# BSPD.net
KiCad netlist of a schematic drawn in EAGLE
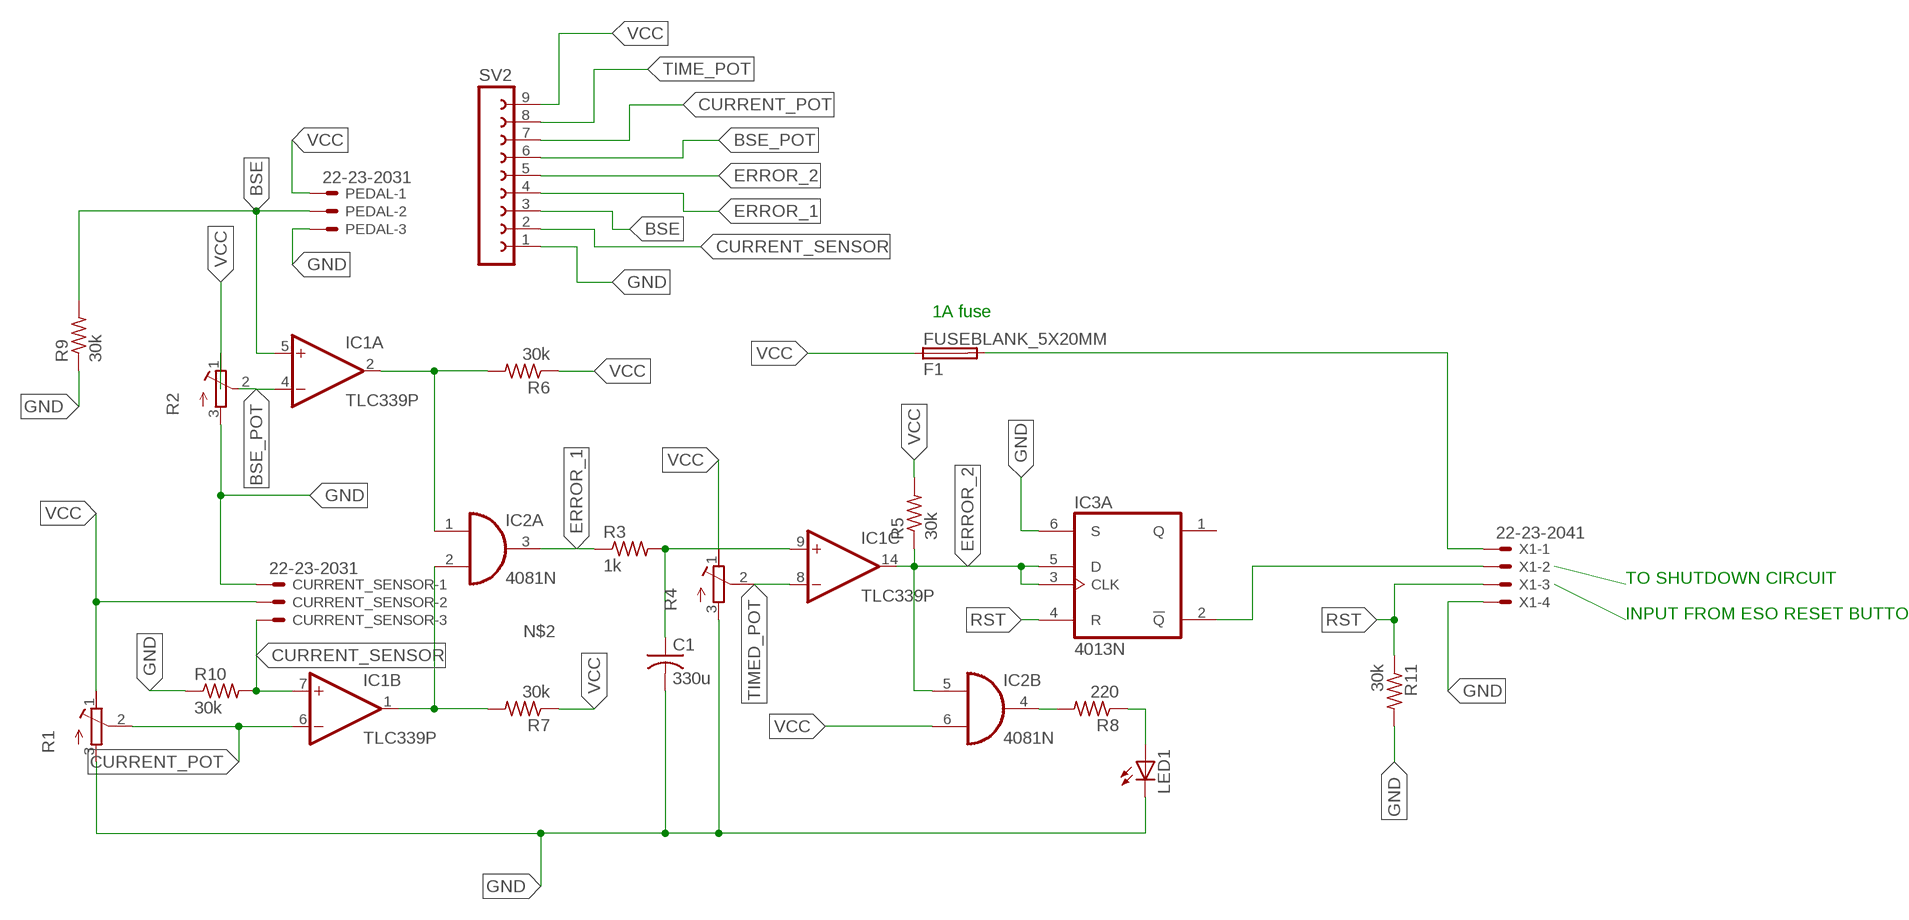
[diagram p0: schematic, sheet 1]

(export (version "E")
  (design (tool "Eeschema 10.0.6"))
  (components
    (comp (ref "C1")
      (value "330u")
      (footprint "eagle-import:C225-108X268")
      (libsource (lib "eagle-import") (part "C-US225-108X268"))
    )
    (comp (ref "CURRENT_SENSOR")
      (value "22-23-2031")
      (footprint "eagle-import:22-23-2031")
      (fields (field (name "MF") "MOLEX"))
      (libsource (lib "eagle-import") (part "22-23-2031"))
    )
    (comp (ref "F1")
      (value "FUSEBLANK_5X20MM")
      (footprint "eagle-import:FUSE_HOLDER_5X20MM")
      (libsource (lib "eagle-import") (part "FUSEBLANK_5X20MM"))
    )
    (comp (ref "IC1")
      (value "TLC339P")
      (footprint "eagle-import:DIL14")
      (libsource (lib "eagle-import") (part "TLC339P"))
    )
    (comp (ref "IC2")
      (value "4081N")
      (footprint "eagle-import:DIL14")
      (libsource (lib "eagle-import") (part "4081N"))
    )
    (comp (ref "IC3")
      (value "4013N")
      (footprint "eagle-import:DIL14")
      (libsource (lib "eagle-import") (part "4013N"))
    )
    (comp (ref "LED1")
      (value "LED5MM")
      (footprint "eagle-import:LED5MM")
      (libsource (lib "eagle-import") (part "LED5MM"))
    )
    (comp (ref "PEDAL")
      (value "22-23-2031")
      (footprint "eagle-import:22-23-2031")
      (fields (field (name "MF") "MOLEX"))
      (libsource (lib "eagle-import") (part "22-23-2031"))
    )
    (comp (ref "R1")
      (value "R-TRIMM3006P")
      (footprint "eagle-import:RTRIM3006P")
      (libsource (lib "eagle-import") (part "R-TRIMM3006P"))
    )
    (comp (ref "R2")
      (value "R-TRIMM43P")
      (footprint "eagle-import:RTRIM43P")
      (libsource (lib "eagle-import") (part "R-TRIMM43P"))
    )
    (comp (ref "R3")
      (value "1k")
      (footprint "eagle-import:0207_12")
      (libsource (lib "eagle-import") (part "R-US_0207/12"))
    )
    (comp (ref "R4")
      (value "R-TRIMM3006P")
      (footprint "eagle-import:RTRIM3006P")
      (libsource (lib "eagle-import") (part "R-TRIMM3006P"))
    )
    (comp (ref "R5")
      (value "30k")
      (footprint "eagle-import:0207_12")
      (libsource (lib "eagle-import") (part "R-US_0207/12"))
    )
    (comp (ref "R6")
      (value "30k")
      (footprint "eagle-import:0207_12")
      (libsource (lib "eagle-import") (part "R-US_0207/12"))
    )
    (comp (ref "R7")
      (value "30k")
      (footprint "eagle-import:0207_12")
      (libsource (lib "eagle-import") (part "R-US_0207/12"))
    )
    (comp (ref "R8")
      (value "220")
      (footprint "eagle-import:0207_12")
      (libsource (lib "eagle-import") (part "R-US_0207/12"))
    )
    (comp (ref "R9")
      (value "30k")
      (footprint "eagle-import:0207_12")
      (libsource (lib "eagle-import") (part "R-US_0207/12"))
    )
    (comp (ref "R10")
      (value "30k")
      (footprint "eagle-import:0207_12")
      (libsource (lib "eagle-import") (part "R-US_0207/12"))
    )
    (comp (ref "R11")
      (value "30k")
      (footprint "eagle-import:0207_12")
      (libsource (lib "eagle-import") (part "R-US_0207/12"))
    )
    (comp (ref "SV2")
      (value "FE09W")
      (footprint "eagle-import:FE09W")
      (libsource (lib "eagle-import") (part "FE09W"))
    )
    (comp (ref "X1")
      (value "22-23-2041")
      (footprint "eagle-import:22-23-2041")
      (fields (field (name "MF") "MOLEX"))
      (libsource (lib "eagle-import") (part "22-23-2041"))
    )
  )
  (nets
    (net (code "1") (name "/N$2") (class "Default")
      (node (ref "IC1") (pin "1") (pinfunction "OUT_1") (pintype "output"))
      (node (ref "IC2") (pin "2") (pinfunction "I1_2") (pintype "input"))
      (node (ref "R7") (pin "2") (pinfunction "2_2") (pintype "passive"))
    )
    (net (code "2") (name "BSE") (class "Default")
      (node (ref "IC1") (pin "5") (pinfunction "+IN_5") (pintype "input"))
      (node (ref "PEDAL") (pin "2") (pinfunction "S_2") (pintype "passive"))
      (node (ref "R9") (pin "2") (pinfunction "2_2") (pintype "passive"))
      (node (ref "SV2") (pin "3") (pinfunction "3_3") (pintype "passive"))
    )
    (net (code "3") (name "BSE_POT") (class "Default")
      (node (ref "IC1") (pin "4") (pinfunction "-IN_4") (pintype "input"))
      (node (ref "R2") (pin "2") (pinfunction "S_2") (pintype "passive"))
      (node (ref "SV2") (pin "6") (pinfunction "6_6") (pintype "passive"))
    )
    (net (code "4") (name "CURRENT_POT") (class "Default")
      (node (ref "IC1") (pin "6") (pinfunction "-IN_6") (pintype "input"))
      (node (ref "R1") (pin "2") (pinfunction "S_2") (pintype "passive"))
      (node (ref "SV2") (pin "7") (pinfunction "7_7") (pintype "passive"))
    )
    (net (code "5") (name "CURRENT_SENSOR") (class "Default")
      (node (ref "CURRENT_SENSOR") (pin "3") (pinfunction "S_3") (pintype "passive"))
      (node (ref "IC1") (pin "7") (pinfunction "+IN_7") (pintype "input"))
      (node (ref "R10") (pin "2") (pinfunction "2_2") (pintype "passive"))
      (node (ref "SV2") (pin "2") (pinfunction "2_2") (pintype "passive"))
    )
    (net (code "6") (name "ERROR_1") (class "Default")
      (node (ref "IC2") (pin "3") (pinfunction "O_3") (pintype "output"))
      (node (ref "R3") (pin "1") (pinfunction "1_1") (pintype "passive"))
      (node (ref "SV2") (pin "4") (pinfunction "4_4") (pintype "passive"))
    )
    (net (code "7") (name "ERROR_2") (class "Default")
      (node (ref "IC1") (pin "14") (pinfunction "OUT_14") (pintype "output"))
      (node (ref "IC2") (pin "5") (pinfunction "I0_5") (pintype "input"))
      (node (ref "IC3") (pin "3") (pinfunction "CLK_3") (pintype "input"))
      (node (ref "IC3") (pin "5") (pinfunction "D_5") (pintype "input"))
      (node (ref "R5") (pin "1") (pinfunction "1_1") (pintype "passive"))
      (node (ref "SV2") (pin "5") (pinfunction "5_5") (pintype "passive"))
    )
    (net (code "8") (name "GND") (class "Default")
      (node (ref "C1") (pin "2") (pinfunction "2_2") (pintype "passive"))
      (node (ref "CURRENT_SENSOR") (pin "1") (pinfunction "S_1") (pintype "passive"))
      (node (ref "IC3") (pin "6") (pinfunction "S_6") (pintype "input"))
      (node (ref "LED1") (pin "K") (pinfunction "C_K") (pintype "passive"))
      (node (ref "PEDAL") (pin "3") (pinfunction "S_3") (pintype "passive"))
      (node (ref "R1") (pin "3") (pinfunction "A_3") (pintype "passive"))
      (node (ref "R10") (pin "1") (pinfunction "1_1") (pintype "passive"))
      (node (ref "R11") (pin "2") (pinfunction "2_2") (pintype "passive"))
      (node (ref "R2") (pin "3") (pinfunction "A_3") (pintype "passive"))
      (node (ref "R4") (pin "3") (pinfunction "A_3") (pintype "passive"))
      (node (ref "R9") (pin "1") (pinfunction "1_1") (pintype "passive"))
      (node (ref "SV2") (pin "1") (pinfunction "1_1") (pintype "passive"))
      (node (ref "X1") (pin "4") (pinfunction "S_4") (pintype "passive"))
    )
    (net (code "9") (name "Net-(IC1A-OUT)") (class "Default")
      (node (ref "IC1") (pin "2") (pinfunction "OUT_2") (pintype "output"))
      (node (ref "IC2") (pin "1") (pinfunction "I0_1") (pintype "input"))
      (node (ref "R6") (pin "2") (pinfunction "2_2") (pintype "passive"))
    )
    (net (code "10") (name "Net-(IC1C-+IN)") (class "Default")
      (node (ref "C1") (pin "1") (pinfunction "1_1") (pintype "passive"))
      (node (ref "IC1") (pin "9") (pinfunction "+IN_9") (pintype "input"))
      (node (ref "R3") (pin "2") (pinfunction "2_2") (pintype "passive"))
    )
    (net (code "11") (name "Net-(IC2B-O)") (class "Default")
      (node (ref "IC2") (pin "4") (pinfunction "O_4") (pintype "output"))
      (node (ref "R8") (pin "2") (pinfunction "2_2") (pintype "passive"))
    )
    (net (code "12") (name "Net-(IC3A-~{Q})") (class "Default")
      (node (ref "IC3") (pin "2") (pinfunction "~{Q}_2") (pintype "output"))
      (node (ref "X1") (pin "2") (pinfunction "S_2") (pintype "passive"))
    )
    (net (code "13") (name "Net-(LED1-PadA)") (class "Default")
      (node (ref "LED1") (pin "A") (pinfunction "A_A") (pintype "passive"))
      (node (ref "R8") (pin "1") (pinfunction "1_1") (pintype "passive"))
    )
    (net (code "14") (name "Net-(X1A-S)") (class "Default")
      (node (ref "F1") (pin "2") (pinfunction "2_2") (pintype "passive"))
      (node (ref "X1") (pin "1") (pinfunction "S_1") (pintype "passive"))
    )
    (net (code "15") (name "RST") (class "Default")
      (node (ref "IC3") (pin "4") (pinfunction "R_4") (pintype "input"))
      (node (ref "R11") (pin "1") (pinfunction "1_1") (pintype "passive"))
      (node (ref "X1") (pin "3") (pinfunction "S_3") (pintype "passive"))
    )
    (net (code "16") (name "TIMED_POT") (class "Default")
      (node (ref "IC1") (pin "8") (pinfunction "-IN_8") (pintype "input"))
      (node (ref "R4") (pin "2") (pinfunction "S_2") (pintype "passive"))
    )
    (net (code "17") (name "TIME_POT") (class "Default")
      (node (ref "SV2") (pin "8") (pinfunction "8_8") (pintype "passive"))
    )
    (net (code "18") (name "VCC") (class "Default")
      (node (ref "CURRENT_SENSOR") (pin "2") (pinfunction "S_2") (pintype "passive"))
      (node (ref "F1") (pin "1") (pinfunction "1_1") (pintype "passive"))
      (node (ref "IC2") (pin "6") (pinfunction "I1_6") (pintype "input"))
      (node (ref "PEDAL") (pin "1") (pinfunction "S_1") (pintype "passive"))
      (node (ref "R1") (pin "1") (pinfunction "E_1") (pintype "passive"))
      (node (ref "R2") (pin "1") (pinfunction "E_1") (pintype "passive"))
      (node (ref "R4") (pin "1") (pinfunction "E_1") (pintype "passive"))
      (node (ref "R5") (pin "2") (pinfunction "2_2") (pintype "passive"))
      (node (ref "R6") (pin "1") (pinfunction "1_1") (pintype "passive"))
      (node (ref "R7") (pin "1") (pinfunction "1_1") (pintype "passive"))
      (node (ref "SV2") (pin "9") (pinfunction "9_9") (pintype "passive"))
    )
    (net (code "19") (name "unconnected-(IC3A-Q-Pad1)") (class "Default")
      (node (ref "IC3") (pin "1") (pinfunction "Q_1") (pintype "output"))
    )
  )
)
